# 04A-010.net
KiCad netlist of a schematic drawn in EAGLE
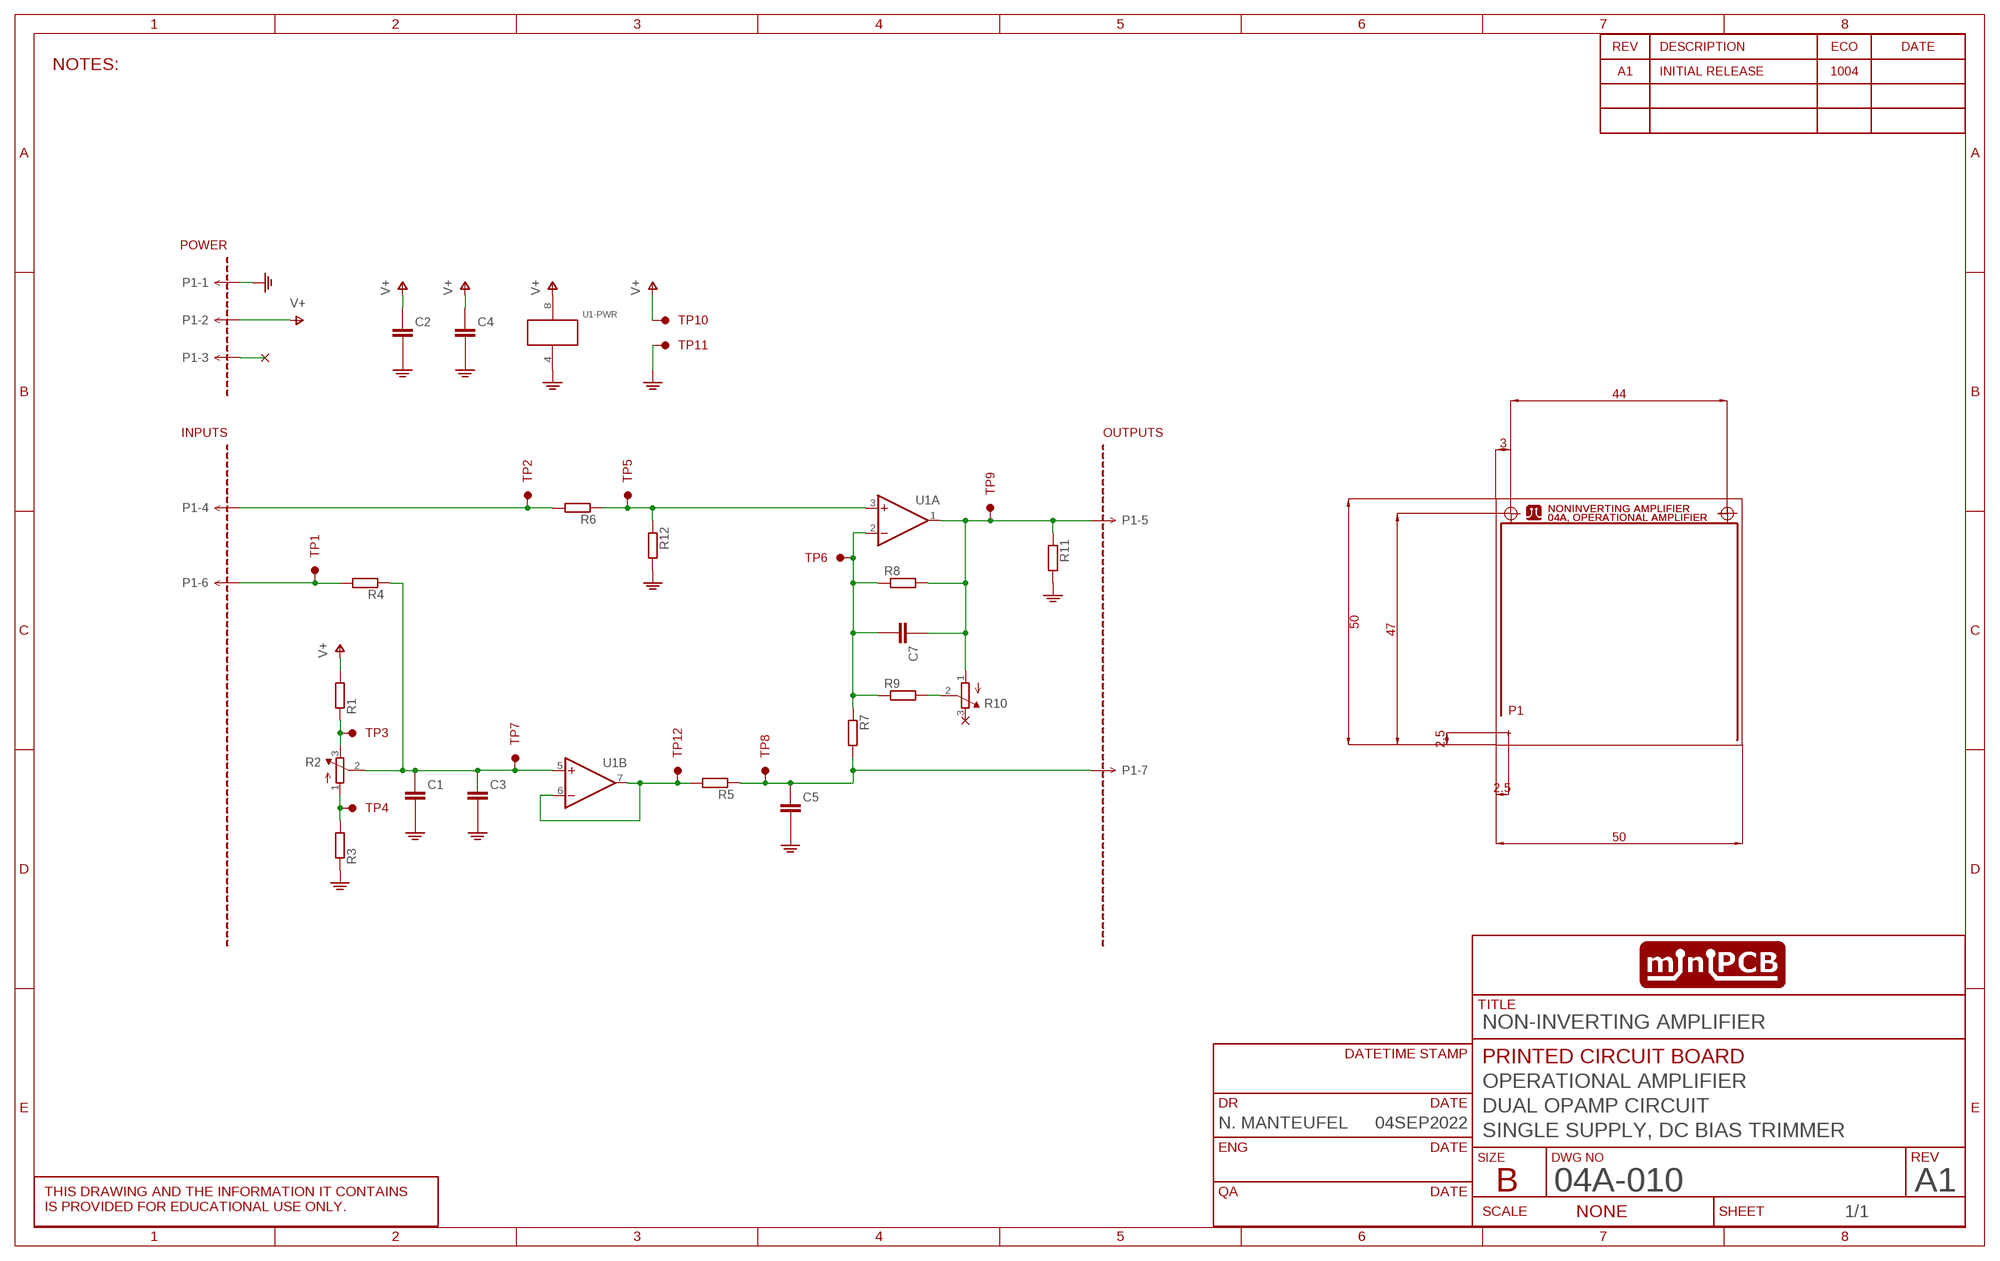
[diagram p0: schematic, sheet 1]

(export (version "E")
  (design (tool "Eeschema 10.0.6"))
  (components
    (comp (ref "C1")
      (value "CAPACITORTHD")
      (footprint "eagle-import:C050-024X044")
      (libsource (lib "eagle-import") (part "CAPACITORTHD"))
    )
    (comp (ref "C2")
      (value "CAPACITORTHD")
      (footprint "eagle-import:C050-024X044")
      (libsource (lib "eagle-import") (part "CAPACITORTHD"))
    )
    (comp (ref "C3")
      (value "CAPACITOR_10")
      (footprint "eagle-import:C5MM")
      (libsource (lib "eagle-import") (part "CAPACITOR_10"))
    )
    (comp (ref "C4")
      (value "CAPACITOR_10")
      (footprint "eagle-import:C5MM")
      (libsource (lib "eagle-import") (part "CAPACITOR_10"))
    )
    (comp (ref "C5")
      (value "CAPACITORTHD")
      (footprint "eagle-import:C050-024X044")
      (libsource (lib "eagle-import") (part "CAPACITORTHD"))
    )
    (comp (ref "C7")
      (value "CAPACITORTHD")
      (footprint "eagle-import:C050-024X044")
      (libsource (lib "eagle-import") (part "CAPACITORTHD"))
    )
    (comp (ref "P1")
      (value "MINIPCB_7P")
      (footprint "eagle-import:PINS_1X7")
      (libsource (lib "eagle-import") (part "MINIPCB_7P"))
    )
    (comp (ref "R1")
      (value "RESISTOR10MM")
      (footprint "eagle-import:0207_10")
      (libsource (lib "eagle-import") (part "RESISTOR10MM"))
    )
    (comp (ref "R2")
      (value "TRIMPOT0.100THD")
      (footprint "eagle-import:TRIM_0100")
      (libsource (lib "eagle-import") (part "TRIMPOT0.100THD"))
    )
    (comp (ref "R3")
      (value "RESISTOR10MM")
      (footprint "eagle-import:0207_10")
      (libsource (lib "eagle-import") (part "RESISTOR10MM"))
    )
    (comp (ref "R4")
      (value "RESISTOR10MM")
      (footprint "eagle-import:0207_10")
      (libsource (lib "eagle-import") (part "RESISTOR10MM"))
    )
    (comp (ref "R5")
      (value "RESISTOR10MM")
      (footprint "eagle-import:0207_10")
      (libsource (lib "eagle-import") (part "RESISTOR10MM"))
    )
    (comp (ref "R6")
      (value "RESISTOR10MM")
      (footprint "eagle-import:0207_10")
      (libsource (lib "eagle-import") (part "RESISTOR10MM"))
    )
    (comp (ref "R7")
      (value "RESISTOR10MM")
      (footprint "eagle-import:0207_10")
      (libsource (lib "eagle-import") (part "RESISTOR10MM"))
    )
    (comp (ref "R8")
      (value "RESISTOR10MM")
      (footprint "eagle-import:0207_10")
      (libsource (lib "eagle-import") (part "RESISTOR10MM"))
    )
    (comp (ref "R9")
      (value "RESISTOR10MM")
      (footprint "eagle-import:0207_10")
      (libsource (lib "eagle-import") (part "RESISTOR10MM"))
    )
    (comp (ref "R10")
      (value "TRIMPOT0.100THD")
      (footprint "eagle-import:TRIM_0100")
      (libsource (lib "eagle-import") (part "TRIMPOT0.100THD"))
    )
    (comp (ref "R11")
      (value "RESISTOR10MM")
      (footprint "eagle-import:0207_10")
      (libsource (lib "eagle-import") (part "RESISTOR10MM"))
    )
    (comp (ref "R12")
      (value "RESISTOR10MM")
      (footprint "eagle-import:0207_10")
      (libsource (lib "eagle-import") (part "RESISTOR10MM"))
    )
    (comp (ref "TP1")
      (value "TESTPOINTKE5000-SMTEXT")
      (footprint "eagle-import:PINS_1_TESTPOINT_KE5000_NOTEXT")
      (libsource (lib "eagle-import") (part "TESTPOINTKE5000-SMTEXT"))
    )
    (comp (ref "TP2")
      (value "TESTPOINTKE5000-SMTEXT")
      (footprint "eagle-import:PINS_1_TESTPOINT_KE5000_NOTEXT")
      (libsource (lib "eagle-import") (part "TESTPOINTKE5000-SMTEXT"))
    )
    (comp (ref "TP3")
      (value "TESTPOINTKE5000-SMTEXT")
      (footprint "eagle-import:PINS_1_TESTPOINT_KE5000_NOTEXT")
      (libsource (lib "eagle-import") (part "TESTPOINTKE5000-SMTEXT"))
    )
    (comp (ref "TP4")
      (value "TESTPOINTKE5000-SMTEXT")
      (footprint "eagle-import:PINS_1_TESTPOINT_KE5000_NOTEXT")
      (libsource (lib "eagle-import") (part "TESTPOINTKE5000-SMTEXT"))
    )
    (comp (ref "TP5")
      (value "TESTPOINTKE5000-SMTEXT")
      (footprint "eagle-import:PINS_1_TESTPOINT_KE5000_NOTEXT")
      (libsource (lib "eagle-import") (part "TESTPOINTKE5000-SMTEXT"))
    )
    (comp (ref "TP6")
      (value "TESTPOINTKE5000-SMTEXT")
      (footprint "eagle-import:PINS_1_TESTPOINT_KE5000_NOTEXT")
      (libsource (lib "eagle-import") (part "TESTPOINTKE5000-SMTEXT"))
    )
    (comp (ref "TP7")
      (value "TESTPOINTKE5000-SMTEXT")
      (footprint "eagle-import:PINS_1_TESTPOINT_KE5000_NOTEXT")
      (libsource (lib "eagle-import") (part "TESTPOINTKE5000-SMTEXT"))
    )
    (comp (ref "TP8")
      (value "TESTPOINTKE5000-SMTEXT")
      (footprint "eagle-import:PINS_1_TESTPOINT_KE5000_NOTEXT")
      (libsource (lib "eagle-import") (part "TESTPOINTKE5000-SMTEXT"))
    )
    (comp (ref "TP9")
      (value "TESTPOINTKE5000-SMTEXT")
      (footprint "eagle-import:PINS_1_TESTPOINT_KE5000_NOTEXT")
      (libsource (lib "eagle-import") (part "TESTPOINTKE5000-SMTEXT"))
    )
    (comp (ref "TP10")
      (value "TESTPOINTKE5000-SMTEXT")
      (footprint "eagle-import:PINS_1_TESTPOINT_KE5000_NOTEXT")
      (libsource (lib "eagle-import") (part "TESTPOINTKE5000-SMTEXT"))
    )
    (comp (ref "TP11")
      (value "TESTPOINTKE5000-SMTEXT")
      (footprint "eagle-import:PINS_1_TESTPOINT_KE5000_NOTEXT")
      (libsource (lib "eagle-import") (part "TESTPOINTKE5000-SMTEXT"))
    )
    (comp (ref "TP12")
      (value "TESTPOINTKE5000-SMTEXT")
      (footprint "eagle-import:PINS_1_TESTPOINT_KE5000_NOTEXT")
      (libsource (lib "eagle-import") (part "TESTPOINTKE5000-SMTEXT"))
    )
    (comp (ref "U$1")
      (value "MINIPCB_50X50")
      (footprint "eagle-import:MINIPCB_0P_50X50MM")
      (fields
        (field (name "TITLE") "TITLE")
        (field (name "CIRCUIT_CATEGORY") "CIRCUIT CATEGORY")
        (field (name "PART_NUMBER") "PART NUMBER")
        (field (name "CIRCUIT_CATEGORY_1") "04A, OPERATIONAL AMPLIFIER")
        (field (name "PART_NUMBER_1") "04A-010")
        (field (name "REVISION") "A1-01")
        (field (name "TITLE_1") "NONINVERTING AMPLIFIER")
      )
      (libsource (lib "eagle-import") (part "MINIPCB_50X50"))
    )
    (comp (ref "U1")
      (value "OPAMP_DUALTHD")
      (footprint "eagle-import:DIL08")
      (libsource (lib "eagle-import") (part "OPAMP_DUALTHD"))
    )
  )
  (nets
    (net (code "1") (name "GND") (class "Default")
      (node (ref "C1") (pin "2") (pinfunction "-_2") (pintype "passive"))
      (node (ref "C2") (pin "2") (pinfunction "-_2") (pintype "passive"))
      (node (ref "C3") (pin "-") (pinfunction "-_-") (pintype "passive"))
      (node (ref "C4") (pin "-") (pinfunction "-_-") (pintype "passive"))
      (node (ref "C5") (pin "2") (pinfunction "-_2") (pintype "passive"))
      (node (ref "P1") (pin "1") (pinfunction "1_1") (pintype "bidirectional"))
      (node (ref "R11") (pin "2") (pinfunction "2_2") (pintype "passive"))
      (node (ref "R12") (pin "2") (pinfunction "2_2") (pintype "passive"))
      (node (ref "R3") (pin "1") (pinfunction "1_1") (pintype "passive"))
      (node (ref "TP11") (pin "1") (pinfunction "1_1") (pintype "bidirectional"))
      (node (ref "U1") (pin "4") (pinfunction "V-_4") (pintype "power_in"))
    )
    (net (code "2") (name "Net-(C1-+)") (class "Default")
      (node (ref "C1") (pin "1") (pinfunction "+_1") (pintype "passive"))
      (node (ref "C3") (pin "+") (pinfunction "+_+") (pintype "passive"))
      (node (ref "R2") (pin "2") (pinfunction "S_2") (pintype "passive"))
      (node (ref "R4") (pin "1") (pinfunction "1_1") (pintype "passive"))
      (node (ref "TP7") (pin "1") (pinfunction "1_1") (pintype "bidirectional"))
      (node (ref "U1") (pin "5") (pinfunction "+IN_5") (pintype "input"))
    )
    (net (code "3") (name "Net-(C5-+)") (class "Default")
      (node (ref "C5") (pin "1") (pinfunction "+_1") (pintype "passive"))
      (node (ref "P1") (pin "7") (pinfunction "1_7") (pintype "bidirectional"))
      (node (ref "R5") (pin "1") (pinfunction "1_1") (pintype "passive"))
      (node (ref "R7") (pin "2") (pinfunction "2_2") (pintype "passive"))
      (node (ref "TP8") (pin "1") (pinfunction "1_1") (pintype "bidirectional"))
    )
    (net (code "4") (name "Net-(C7-+)") (class "Default")
      (node (ref "C7") (pin "1") (pinfunction "+_1") (pintype "passive"))
      (node (ref "P1") (pin "5") (pinfunction "1_5") (pintype "bidirectional"))
      (node (ref "R10") (pin "1") (pinfunction "A_1") (pintype "passive"))
      (node (ref "R11") (pin "1") (pinfunction "1_1") (pintype "passive"))
      (node (ref "R8") (pin "2") (pinfunction "2_2") (pintype "passive"))
      (node (ref "TP9") (pin "1") (pinfunction "1_1") (pintype "bidirectional"))
      (node (ref "U1") (pin "1") (pinfunction "OUT_1") (pintype "output"))
    )
    (net (code "5") (name "Net-(C7--)") (class "Default")
      (node (ref "C7") (pin "2") (pinfunction "-_2") (pintype "passive"))
      (node (ref "R7") (pin "1") (pinfunction "1_1") (pintype "passive"))
      (node (ref "R8") (pin "1") (pinfunction "1_1") (pintype "passive"))
      (node (ref "R9") (pin "1") (pinfunction "1_1") (pintype "passive"))
      (node (ref "TP6") (pin "1") (pinfunction "1_1") (pintype "bidirectional"))
      (node (ref "U1") (pin "2") (pinfunction "-IN_2") (pintype "input"))
    )
    (net (code "6") (name "Net-(P1D-1)") (class "Default")
      (node (ref "P1") (pin "4") (pinfunction "1_4") (pintype "bidirectional"))
      (node (ref "R6") (pin "2") (pinfunction "2_2") (pintype "passive"))
      (node (ref "TP2") (pin "1") (pinfunction "1_1") (pintype "bidirectional"))
    )
    (net (code "7") (name "Net-(P1F-1)") (class "Default")
      (node (ref "P1") (pin "6") (pinfunction "1_6") (pintype "bidirectional"))
      (node (ref "R4") (pin "2") (pinfunction "2_2") (pintype "passive"))
      (node (ref "TP1") (pin "1") (pinfunction "1_1") (pintype "bidirectional"))
    )
    (net (code "8") (name "Net-(R2-A)") (class "Default")
      (node (ref "R2") (pin "1") (pinfunction "A_1") (pintype "passive"))
      (node (ref "R3") (pin "2") (pinfunction "2_2") (pintype "passive"))
      (node (ref "TP4") (pin "1") (pinfunction "1_1") (pintype "bidirectional"))
    )
    (net (code "9") (name "Net-(R2-E)") (class "Default")
      (node (ref "R1") (pin "1") (pinfunction "1_1") (pintype "passive"))
      (node (ref "R2") (pin "3") (pinfunction "E_3") (pintype "passive"))
      (node (ref "TP3") (pin "1") (pinfunction "1_1") (pintype "bidirectional"))
    )
    (net (code "10") (name "Net-(R10-S)") (class "Default")
      (node (ref "R10") (pin "2") (pinfunction "S_2") (pintype "passive"))
      (node (ref "R9") (pin "2") (pinfunction "2_2") (pintype "passive"))
    )
    (net (code "11") (name "Net-(U1B-+IN)") (class "Default")
      (node (ref "R12") (pin "1") (pinfunction "1_1") (pintype "passive"))
      (node (ref "R6") (pin "1") (pinfunction "1_1") (pintype "passive"))
      (node (ref "TP5") (pin "1") (pinfunction "1_1") (pintype "bidirectional"))
      (node (ref "U1") (pin "3") (pinfunction "+IN_3") (pintype "input"))
    )
    (net (code "12") (name "Net-(U1C--IN)") (class "Default")
      (node (ref "R5") (pin "2") (pinfunction "2_2") (pintype "passive"))
      (node (ref "TP12") (pin "1") (pinfunction "1_1") (pintype "bidirectional"))
      (node (ref "U1") (pin "6") (pinfunction "-IN_6") (pintype "input"))
      (node (ref "U1") (pin "7") (pinfunction "OUT_7") (pintype "output"))
    )
    (net (code "13") (name "V+") (class "Default")
      (node (ref "C2") (pin "1") (pinfunction "+_1") (pintype "passive"))
      (node (ref "C4") (pin "+") (pinfunction "+_+") (pintype "passive"))
      (node (ref "P1") (pin "2") (pinfunction "1_2") (pintype "bidirectional"))
      (node (ref "R1") (pin "2") (pinfunction "2_2") (pintype "passive"))
      (node (ref "TP10") (pin "1") (pinfunction "1_1") (pintype "bidirectional"))
      (node (ref "U1") (pin "8") (pinfunction "V+_8") (pintype "power_in"))
    )
    (net (code "14") (name "unconnected-(P1C-1-Pad3)") (class "Default")
      (node (ref "P1") (pin "3") (pinfunction "1_3") (pintype "bidirectional"))
    )
    (net (code "15") (name "unconnected-(R10-E-Pad3)") (class "Default")
      (node (ref "R10") (pin "3") (pinfunction "E_3") (pintype "passive"))
    )
  )
)
